# Tablero_Potencia.net
KiCad netlist of a schematic drawn in EAGLE
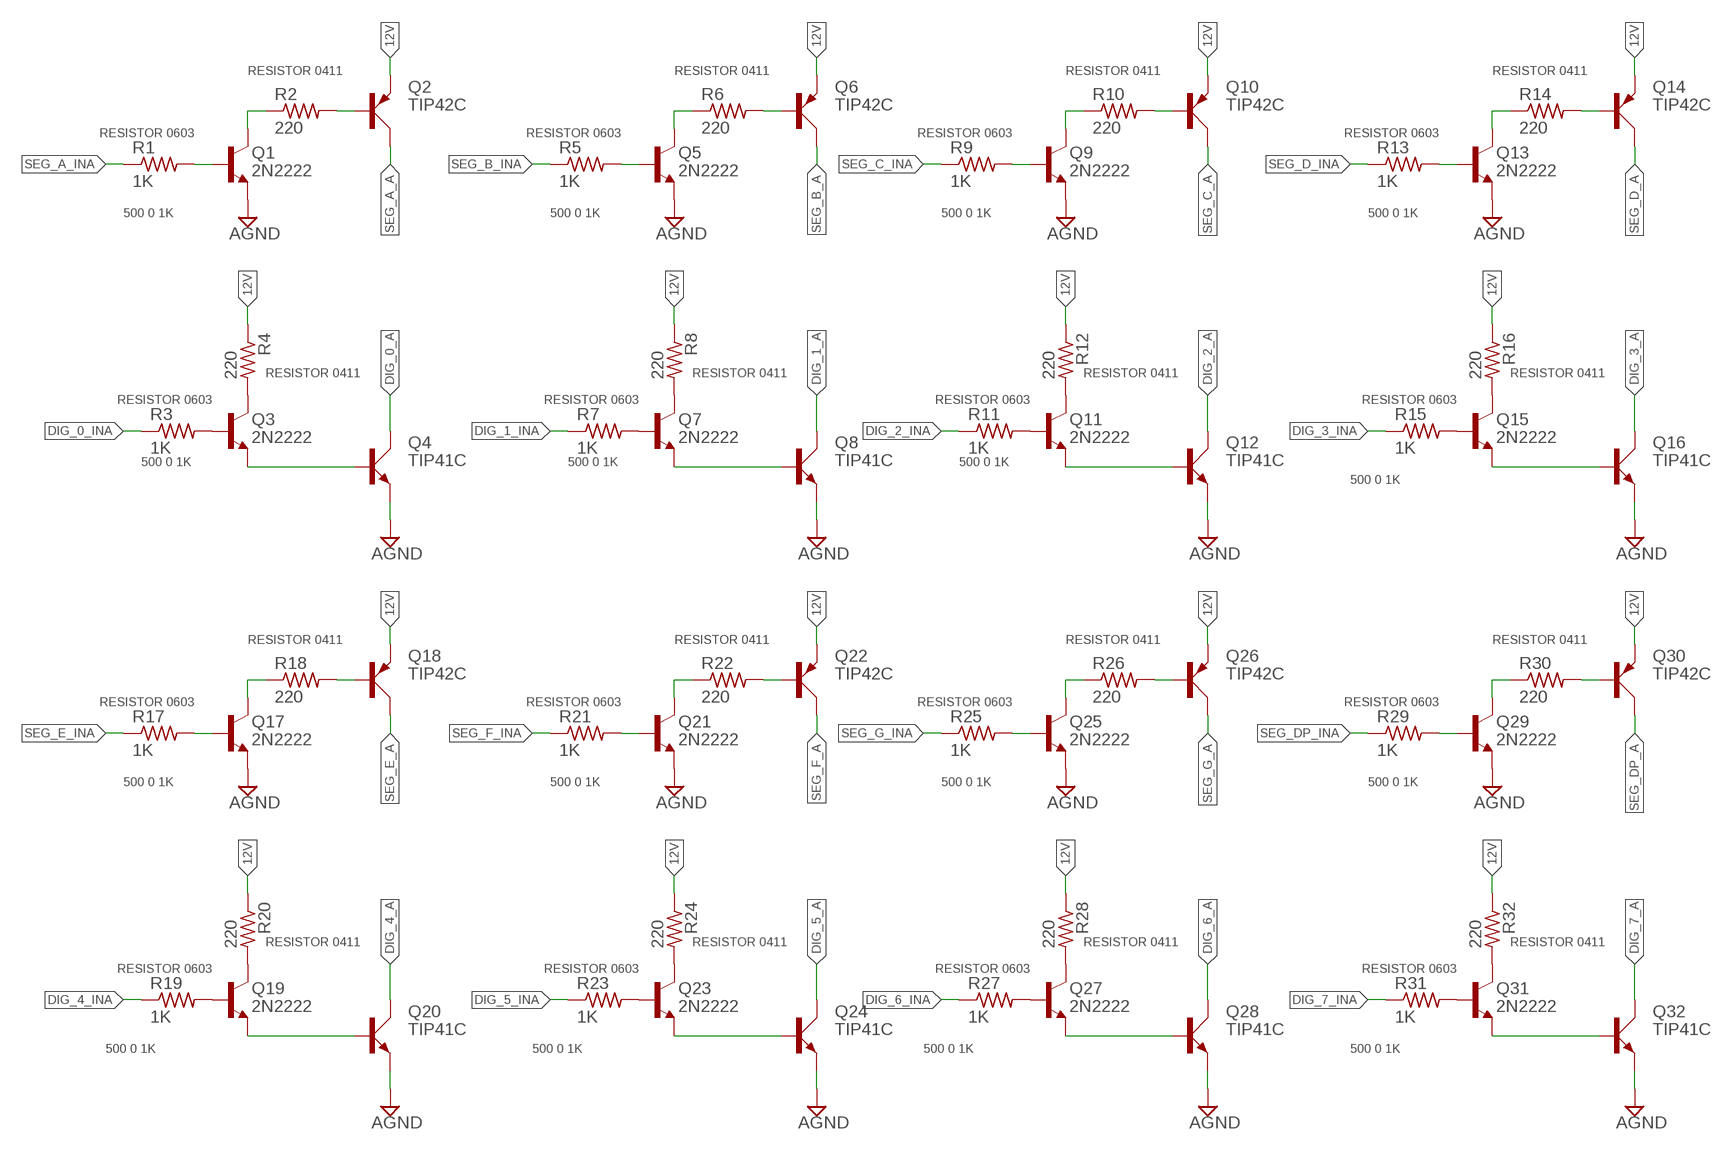
[diagram p0: schematic, sheet 1, part 1 of 2]
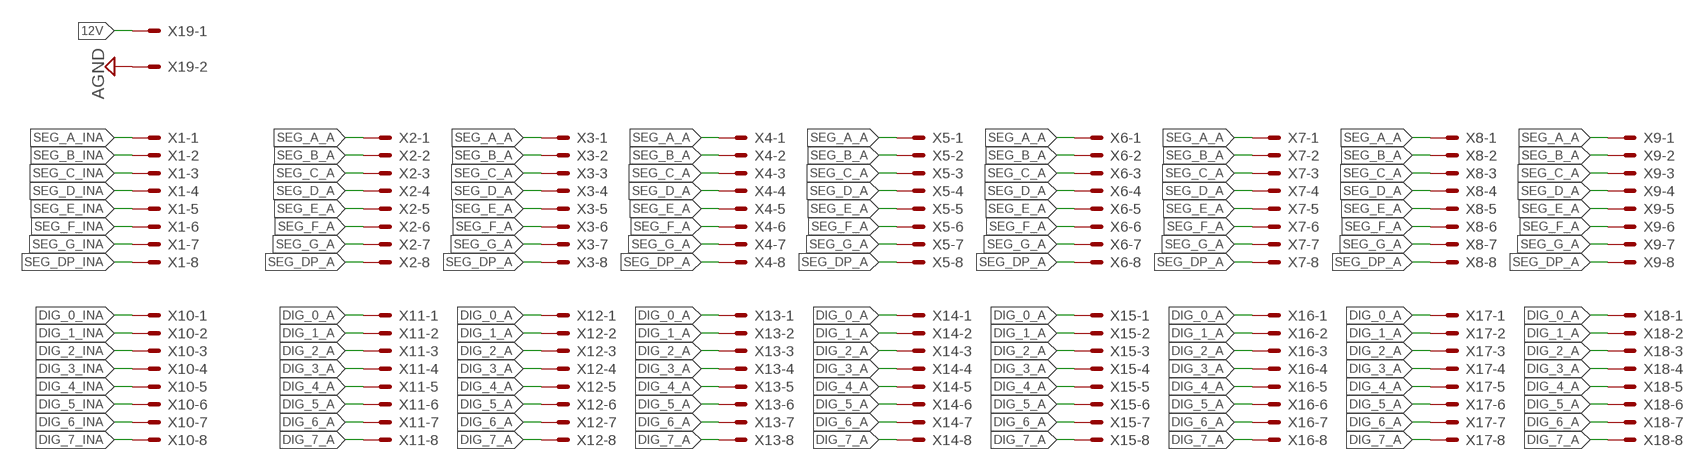
[diagram p1: schematic, sheet 1, part 2 of 2]

(export (version "E")
  (design (tool "Eeschema 10.0.6"))
  (components
    (comp (ref "Q1")
      (value "2N2222")
      (footprint "eagle-import:TO92")
      (libsource (lib "eagle-import") (part "BJT-NPNTO92"))
    )
    (comp (ref "Q2")
      (value "TIP42C")
      (footprint "eagle-import:TO220AV")
      (libsource (lib "eagle-import") (part "TIP42C"))
    )
    (comp (ref "Q3")
      (value "2N2222")
      (footprint "eagle-import:TO92")
      (libsource (lib "eagle-import") (part "BJT-NPNTO92"))
    )
    (comp (ref "Q4")
      (value "TIP41C")
      (footprint "eagle-import:TO220AV")
      (libsource (lib "eagle-import") (part "TIP41C"))
    )
    (comp (ref "Q5")
      (value "2N2222")
      (footprint "eagle-import:TO92")
      (libsource (lib "eagle-import") (part "BJT-NPNTO92"))
    )
    (comp (ref "Q6")
      (value "TIP42C")
      (footprint "eagle-import:TO220AV")
      (libsource (lib "eagle-import") (part "TIP42C"))
    )
    (comp (ref "Q7")
      (value "2N2222")
      (footprint "eagle-import:TO92")
      (libsource (lib "eagle-import") (part "BJT-NPNTO92"))
    )
    (comp (ref "Q8")
      (value "TIP41C")
      (footprint "eagle-import:TO220AV")
      (libsource (lib "eagle-import") (part "TIP41C"))
    )
    (comp (ref "Q9")
      (value "2N2222")
      (footprint "eagle-import:TO92")
      (libsource (lib "eagle-import") (part "BJT-NPNTO92"))
    )
    (comp (ref "Q10")
      (value "TIP42C")
      (footprint "eagle-import:TO220AV")
      (libsource (lib "eagle-import") (part "TIP42C"))
    )
    (comp (ref "Q11")
      (value "2N2222")
      (footprint "eagle-import:TO92")
      (libsource (lib "eagle-import") (part "BJT-NPNTO92"))
    )
    (comp (ref "Q12")
      (value "TIP41C")
      (footprint "eagle-import:TO220AV")
      (libsource (lib "eagle-import") (part "TIP41C"))
    )
    (comp (ref "Q13")
      (value "2N2222")
      (footprint "eagle-import:TO92")
      (libsource (lib "eagle-import") (part "BJT-NPNTO92"))
    )
    (comp (ref "Q14")
      (value "TIP42C")
      (footprint "eagle-import:TO220AV")
      (libsource (lib "eagle-import") (part "TIP42C"))
    )
    (comp (ref "Q15")
      (value "2N2222")
      (footprint "eagle-import:TO92")
      (libsource (lib "eagle-import") (part "BJT-NPNTO92"))
    )
    (comp (ref "Q16")
      (value "TIP41C")
      (footprint "eagle-import:TO220AV")
      (libsource (lib "eagle-import") (part "TIP41C"))
    )
    (comp (ref "Q17")
      (value "2N2222")
      (footprint "eagle-import:TO92")
      (libsource (lib "eagle-import") (part "BJT-NPNTO92"))
    )
    (comp (ref "Q18")
      (value "TIP42C")
      (footprint "eagle-import:TO220AV")
      (libsource (lib "eagle-import") (part "TIP42C"))
    )
    (comp (ref "Q19")
      (value "2N2222")
      (footprint "eagle-import:TO92")
      (libsource (lib "eagle-import") (part "BJT-NPNTO92"))
    )
    (comp (ref "Q20")
      (value "TIP41C")
      (footprint "eagle-import:TO220AV")
      (libsource (lib "eagle-import") (part "TIP41C"))
    )
    (comp (ref "Q21")
      (value "2N2222")
      (footprint "eagle-import:TO92")
      (libsource (lib "eagle-import") (part "BJT-NPNTO92"))
    )
    (comp (ref "Q22")
      (value "TIP42C")
      (footprint "eagle-import:TO220AV")
      (libsource (lib "eagle-import") (part "TIP42C"))
    )
    (comp (ref "Q23")
      (value "2N2222")
      (footprint "eagle-import:TO92")
      (libsource (lib "eagle-import") (part "BJT-NPNTO92"))
    )
    (comp (ref "Q24")
      (value "TIP41C")
      (footprint "eagle-import:TO220AV")
      (libsource (lib "eagle-import") (part "TIP41C"))
    )
    (comp (ref "Q25")
      (value "2N2222")
      (footprint "eagle-import:TO92")
      (libsource (lib "eagle-import") (part "BJT-NPNTO92"))
    )
    (comp (ref "Q26")
      (value "TIP42C")
      (footprint "eagle-import:TO220AV")
      (libsource (lib "eagle-import") (part "TIP42C"))
    )
    (comp (ref "Q27")
      (value "2N2222")
      (footprint "eagle-import:TO92")
      (libsource (lib "eagle-import") (part "BJT-NPNTO92"))
    )
    (comp (ref "Q28")
      (value "TIP41C")
      (footprint "eagle-import:TO220AV")
      (libsource (lib "eagle-import") (part "TIP41C"))
    )
    (comp (ref "Q29")
      (value "2N2222")
      (footprint "eagle-import:TO92")
      (libsource (lib "eagle-import") (part "BJT-NPNTO92"))
    )
    (comp (ref "Q30")
      (value "TIP42C")
      (footprint "eagle-import:TO220AV")
      (libsource (lib "eagle-import") (part "TIP42C"))
    )
    (comp (ref "Q31")
      (value "2N2222")
      (footprint "eagle-import:TO92")
      (libsource (lib "eagle-import") (part "BJT-NPNTO92"))
    )
    (comp (ref "Q32")
      (value "TIP41C")
      (footprint "eagle-import:TO220AV")
      (libsource (lib "eagle-import") (part "TIP41C"))
    )
    (comp (ref "R1")
      (value "1K")
      (footprint "eagle-import:R0603")
      (libsource (lib "eagle-import") (part "R-US_R0603"))
    )
    (comp (ref "R2")
      (value "220")
      (footprint "eagle-import:0411_15")
      (libsource (lib "eagle-import") (part "R-US_0411/15"))
    )
    (comp (ref "R3")
      (value "1K")
      (footprint "eagle-import:R0603")
      (libsource (lib "eagle-import") (part "R-US_R0603"))
    )
    (comp (ref "R4")
      (value "220")
      (footprint "eagle-import:0411_15")
      (libsource (lib "eagle-import") (part "R-US_0411/15"))
    )
    (comp (ref "R5")
      (value "1K")
      (footprint "eagle-import:R0603")
      (libsource (lib "eagle-import") (part "R-US_R0603"))
    )
    (comp (ref "R6")
      (value "220")
      (footprint "eagle-import:0411_15")
      (libsource (lib "eagle-import") (part "R-US_0411/15"))
    )
    (comp (ref "R7")
      (value "1K")
      (footprint "eagle-import:R0603")
      (libsource (lib "eagle-import") (part "R-US_R0603"))
    )
    (comp (ref "R8")
      (value "220")
      (footprint "eagle-import:0411_15")
      (libsource (lib "eagle-import") (part "R-US_0411/15"))
    )
    (comp (ref "R9")
      (value "1K")
      (footprint "eagle-import:R0603")
      (libsource (lib "eagle-import") (part "R-US_R0603"))
    )
    (comp (ref "R10")
      (value "220")
      (footprint "eagle-import:0411_15")
      (libsource (lib "eagle-import") (part "R-US_0411/15"))
    )
    (comp (ref "R11")
      (value "1K")
      (footprint "eagle-import:R0603")
      (libsource (lib "eagle-import") (part "R-US_R0603"))
    )
    (comp (ref "R12")
      (value "220")
      (footprint "eagle-import:0411_15")
      (libsource (lib "eagle-import") (part "R-US_0411/15"))
    )
    (comp (ref "R13")
      (value "1K")
      (footprint "eagle-import:R0603")
      (libsource (lib "eagle-import") (part "R-US_R0603"))
    )
    (comp (ref "R14")
      (value "220")
      (footprint "eagle-import:0411_15")
      (libsource (lib "eagle-import") (part "R-US_0411/15"))
    )
    (comp (ref "R15")
      (value "1K")
      (footprint "eagle-import:R0603")
      (libsource (lib "eagle-import") (part "R-US_R0603"))
    )
    (comp (ref "R16")
      (value "220")
      (footprint "eagle-import:0411_15")
      (libsource (lib "eagle-import") (part "R-US_0411/15"))
    )
    (comp (ref "R17")
      (value "1K")
      (footprint "eagle-import:R0603")
      (libsource (lib "eagle-import") (part "R-US_R0603"))
    )
    (comp (ref "R18")
      (value "220")
      (footprint "eagle-import:0411_15")
      (libsource (lib "eagle-import") (part "R-US_0411/15"))
    )
    (comp (ref "R19")
      (value "1K")
      (footprint "eagle-import:R0603")
      (libsource (lib "eagle-import") (part "R-US_R0603"))
    )
    (comp (ref "R20")
      (value "220")
      (footprint "eagle-import:0411_15")
      (libsource (lib "eagle-import") (part "R-US_0411/15"))
    )
    (comp (ref "R21")
      (value "1K")
      (footprint "eagle-import:R0603")
      (libsource (lib "eagle-import") (part "R-US_R0603"))
    )
    (comp (ref "R22")
      (value "220")
      (footprint "eagle-import:0411_15")
      (libsource (lib "eagle-import") (part "R-US_0411/15"))
    )
    (comp (ref "R23")
      (value "1K")
      (footprint "eagle-import:R0603")
      (libsource (lib "eagle-import") (part "R-US_R0603"))
    )
    (comp (ref "R24")
      (value "220")
      (footprint "eagle-import:0411_15")
      (libsource (lib "eagle-import") (part "R-US_0411/15"))
    )
    (comp (ref "R25")
      (value "1K")
      (footprint "eagle-import:R0603")
      (libsource (lib "eagle-import") (part "R-US_R0603"))
    )
    (comp (ref "R26")
      (value "220")
      (footprint "eagle-import:0411_15")
      (libsource (lib "eagle-import") (part "R-US_0411/15"))
    )
    (comp (ref "R27")
      (value "1K")
      (footprint "eagle-import:R0603")
      (libsource (lib "eagle-import") (part "R-US_R0603"))
    )
    (comp (ref "R28")
      (value "220")
      (footprint "eagle-import:0411_15")
      (libsource (lib "eagle-import") (part "R-US_0411/15"))
    )
    (comp (ref "R29")
      (value "1K")
      (footprint "eagle-import:R0603")
      (libsource (lib "eagle-import") (part "R-US_R0603"))
    )
    (comp (ref "R30")
      (value "220")
      (footprint "eagle-import:0411_15")
      (libsource (lib "eagle-import") (part "R-US_0411/15"))
    )
    (comp (ref "R31")
      (value "1K")
      (footprint "eagle-import:R0603")
      (libsource (lib "eagle-import") (part "R-US_R0603"))
    )
    (comp (ref "R32")
      (value "220")
      (footprint "eagle-import:0411_15")
      (libsource (lib "eagle-import") (part "R-US_0411/15"))
    )
    (comp (ref "X1")
      (value "KK-156-8")
      (footprint "eagle-import:KK-156-8")
      (fields (field (name "MF") "MOLEX"))
      (libsource (lib "eagle-import") (part "KK-156-8"))
    )
    (comp (ref "X2")
      (value "KK-156-8")
      (footprint "eagle-import:KK-156-8")
      (fields (field (name "MF") "MOLEX"))
      (libsource (lib "eagle-import") (part "KK-156-8"))
    )
    (comp (ref "X3")
      (value "KK-156-8")
      (footprint "eagle-import:KK-156-8")
      (fields (field (name "MF") "MOLEX"))
      (libsource (lib "eagle-import") (part "KK-156-8"))
    )
    (comp (ref "X4")
      (value "KK-156-8")
      (footprint "eagle-import:KK-156-8")
      (fields (field (name "MF") "MOLEX"))
      (libsource (lib "eagle-import") (part "KK-156-8"))
    )
    (comp (ref "X5")
      (value "KK-156-8")
      (footprint "eagle-import:KK-156-8")
      (fields (field (name "MF") "MOLEX"))
      (libsource (lib "eagle-import") (part "KK-156-8"))
    )
    (comp (ref "X6")
      (value "KK-156-8")
      (footprint "eagle-import:KK-156-8")
      (fields (field (name "MF") "MOLEX"))
      (libsource (lib "eagle-import") (part "KK-156-8"))
    )
    (comp (ref "X7")
      (value "KK-156-8")
      (footprint "eagle-import:KK-156-8")
      (fields (field (name "MF") "MOLEX"))
      (libsource (lib "eagle-import") (part "KK-156-8"))
    )
    (comp (ref "X8")
      (value "KK-156-8")
      (footprint "eagle-import:KK-156-8")
      (fields (field (name "MF") "MOLEX"))
      (libsource (lib "eagle-import") (part "KK-156-8"))
    )
    (comp (ref "X9")
      (value "KK-156-8")
      (footprint "eagle-import:KK-156-8")
      (fields (field (name "MF") "MOLEX"))
      (libsource (lib "eagle-import") (part "KK-156-8"))
    )
    (comp (ref "X10")
      (value "KK-156-8")
      (footprint "eagle-import:KK-156-8")
      (fields (field (name "MF") "MOLEX"))
      (libsource (lib "eagle-import") (part "KK-156-8"))
    )
    (comp (ref "X11")
      (value "KK-156-8")
      (footprint "eagle-import:KK-156-8")
      (fields (field (name "MF") "MOLEX"))
      (libsource (lib "eagle-import") (part "KK-156-8"))
    )
    (comp (ref "X12")
      (value "KK-156-8")
      (footprint "eagle-import:KK-156-8")
      (fields (field (name "MF") "MOLEX"))
      (libsource (lib "eagle-import") (part "KK-156-8"))
    )
    (comp (ref "X13")
      (value "KK-156-8")
      (footprint "eagle-import:KK-156-8")
      (fields (field (name "MF") "MOLEX"))
      (libsource (lib "eagle-import") (part "KK-156-8"))
    )
    (comp (ref "X14")
      (value "KK-156-8")
      (footprint "eagle-import:KK-156-8")
      (fields (field (name "MF") "MOLEX"))
      (libsource (lib "eagle-import") (part "KK-156-8"))
    )
    (comp (ref "X15")
      (value "KK-156-8")
      (footprint "eagle-import:KK-156-8")
      (fields (field (name "MF") "MOLEX"))
      (libsource (lib "eagle-import") (part "KK-156-8"))
    )
    (comp (ref "X16")
      (value "KK-156-8")
      (footprint "eagle-import:KK-156-8")
      (fields (field (name "MF") "MOLEX"))
      (libsource (lib "eagle-import") (part "KK-156-8"))
    )
    (comp (ref "X17")
      (value "KK-156-8")
      (footprint "eagle-import:KK-156-8")
      (fields (field (name "MF") "MOLEX"))
      (libsource (lib "eagle-import") (part "KK-156-8"))
    )
    (comp (ref "X18")
      (value "KK-156-8")
      (footprint "eagle-import:KK-156-8")
      (fields (field (name "MF") "MOLEX"))
      (libsource (lib "eagle-import") (part "KK-156-8"))
    )
    (comp (ref "X19")
      (value "KK-156-2")
      (footprint "eagle-import:KK-156-2")
      (fields (field (name "MF") "MOLEX"))
      (libsource (lib "eagle-import") (part "KK-156-2"))
    )
  )
  (nets
    (net (code "1") (name "12V") (class "Default")
      (node (ref "Q10") (pin "E") (pinfunction "E_E") (pintype "passive"))
      (node (ref "Q14") (pin "E") (pinfunction "E_E") (pintype "passive"))
      (node (ref "Q18") (pin "E") (pinfunction "E_E") (pintype "passive"))
      (node (ref "Q2") (pin "E") (pinfunction "E_E") (pintype "passive"))
      (node (ref "Q22") (pin "E") (pinfunction "E_E") (pintype "passive"))
      (node (ref "Q26") (pin "E") (pinfunction "E_E") (pintype "passive"))
      (node (ref "Q30") (pin "E") (pinfunction "E_E") (pintype "passive"))
      (node (ref "Q6") (pin "E") (pinfunction "E_E") (pintype "passive"))
      (node (ref "R12") (pin "1") (pinfunction "1_1") (pintype "passive"))
      (node (ref "R16") (pin "1") (pinfunction "1_1") (pintype "passive"))
      (node (ref "R20") (pin "1") (pinfunction "1_1") (pintype "passive"))
      (node (ref "R24") (pin "1") (pinfunction "1_1") (pintype "passive"))
      (node (ref "R28") (pin "1") (pinfunction "1_1") (pintype "passive"))
      (node (ref "R32") (pin "1") (pinfunction "1_1") (pintype "passive"))
      (node (ref "R4") (pin "1") (pinfunction "1_1") (pintype "passive"))
      (node (ref "R8") (pin "1") (pinfunction "1_1") (pintype "passive"))
      (node (ref "X19") (pin "1") (pinfunction "S_1") (pintype "passive"))
    )
    (net (code "2") (name "AGND") (class "Default")
      (node (ref "Q1") (pin "3") (pinfunction "E_3") (pintype "passive"))
      (node (ref "Q12") (pin "E") (pinfunction "E_E") (pintype "passive"))
      (node (ref "Q13") (pin "3") (pinfunction "E_3") (pintype "passive"))
      (node (ref "Q16") (pin "E") (pinfunction "E_E") (pintype "passive"))
      (node (ref "Q17") (pin "3") (pinfunction "E_3") (pintype "passive"))
      (node (ref "Q20") (pin "E") (pinfunction "E_E") (pintype "passive"))
      (node (ref "Q21") (pin "3") (pinfunction "E_3") (pintype "passive"))
      (node (ref "Q24") (pin "E") (pinfunction "E_E") (pintype "passive"))
      (node (ref "Q25") (pin "3") (pinfunction "E_3") (pintype "passive"))
      (node (ref "Q28") (pin "E") (pinfunction "E_E") (pintype "passive"))
      (node (ref "Q29") (pin "3") (pinfunction "E_3") (pintype "passive"))
      (node (ref "Q32") (pin "E") (pinfunction "E_E") (pintype "passive"))
      (node (ref "Q4") (pin "E") (pinfunction "E_E") (pintype "passive"))
      (node (ref "Q5") (pin "3") (pinfunction "E_3") (pintype "passive"))
      (node (ref "Q8") (pin "E") (pinfunction "E_E") (pintype "passive"))
      (node (ref "Q9") (pin "3") (pinfunction "E_3") (pintype "passive"))
      (node (ref "X19") (pin "2") (pinfunction "S_2") (pintype "passive"))
    )
    (net (code "3") (name "DIG_0_A") (class "Default")
      (node (ref "Q4") (pin "C") (pinfunction "C_C") (pintype "passive"))
      (node (ref "X11") (pin "1") (pinfunction "S_1") (pintype "passive"))
      (node (ref "X12") (pin "1") (pinfunction "S_1") (pintype "passive"))
      (node (ref "X13") (pin "1") (pinfunction "S_1") (pintype "passive"))
      (node (ref "X14") (pin "1") (pinfunction "S_1") (pintype "passive"))
      (node (ref "X15") (pin "1") (pinfunction "S_1") (pintype "passive"))
      (node (ref "X16") (pin "1") (pinfunction "S_1") (pintype "passive"))
      (node (ref "X17") (pin "1") (pinfunction "S_1") (pintype "passive"))
      (node (ref "X18") (pin "1") (pinfunction "S_1") (pintype "passive"))
    )
    (net (code "4") (name "DIG_0_INA") (class "Default")
      (node (ref "R3") (pin "1") (pinfunction "1_1") (pintype "passive"))
      (node (ref "X10") (pin "1") (pinfunction "S_1") (pintype "passive"))
    )
    (net (code "5") (name "DIG_1_A") (class "Default")
      (node (ref "Q8") (pin "C") (pinfunction "C_C") (pintype "passive"))
      (node (ref "X11") (pin "2") (pinfunction "S_2") (pintype "passive"))
      (node (ref "X12") (pin "2") (pinfunction "S_2") (pintype "passive"))
      (node (ref "X13") (pin "2") (pinfunction "S_2") (pintype "passive"))
      (node (ref "X14") (pin "2") (pinfunction "S_2") (pintype "passive"))
      (node (ref "X15") (pin "2") (pinfunction "S_2") (pintype "passive"))
      (node (ref "X16") (pin "2") (pinfunction "S_2") (pintype "passive"))
      (node (ref "X17") (pin "2") (pinfunction "S_2") (pintype "passive"))
      (node (ref "X18") (pin "2") (pinfunction "S_2") (pintype "passive"))
    )
    (net (code "6") (name "DIG_1_INA") (class "Default")
      (node (ref "R7") (pin "1") (pinfunction "1_1") (pintype "passive"))
      (node (ref "X10") (pin "2") (pinfunction "S_2") (pintype "passive"))
    )
    (net (code "7") (name "DIG_2_A") (class "Default")
      (node (ref "Q12") (pin "C") (pinfunction "C_C") (pintype "passive"))
      (node (ref "X11") (pin "3") (pinfunction "S_3") (pintype "passive"))
      (node (ref "X12") (pin "3") (pinfunction "S_3") (pintype "passive"))
      (node (ref "X13") (pin "3") (pinfunction "S_3") (pintype "passive"))
      (node (ref "X14") (pin "3") (pinfunction "S_3") (pintype "passive"))
      (node (ref "X15") (pin "3") (pinfunction "S_3") (pintype "passive"))
      (node (ref "X16") (pin "3") (pinfunction "S_3") (pintype "passive"))
      (node (ref "X17") (pin "3") (pinfunction "S_3") (pintype "passive"))
      (node (ref "X18") (pin "3") (pinfunction "S_3") (pintype "passive"))
    )
    (net (code "8") (name "DIG_2_INA") (class "Default")
      (node (ref "R11") (pin "1") (pinfunction "1_1") (pintype "passive"))
      (node (ref "X10") (pin "3") (pinfunction "S_3") (pintype "passive"))
    )
    (net (code "9") (name "DIG_3_A") (class "Default")
      (node (ref "Q16") (pin "C") (pinfunction "C_C") (pintype "passive"))
      (node (ref "X11") (pin "4") (pinfunction "S_4") (pintype "passive"))
      (node (ref "X12") (pin "4") (pinfunction "S_4") (pintype "passive"))
      (node (ref "X13") (pin "4") (pinfunction "S_4") (pintype "passive"))
      (node (ref "X14") (pin "4") (pinfunction "S_4") (pintype "passive"))
      (node (ref "X15") (pin "4") (pinfunction "S_4") (pintype "passive"))
      (node (ref "X16") (pin "4") (pinfunction "S_4") (pintype "passive"))
      (node (ref "X17") (pin "4") (pinfunction "S_4") (pintype "passive"))
      (node (ref "X18") (pin "4") (pinfunction "S_4") (pintype "passive"))
    )
    (net (code "10") (name "DIG_3_INA") (class "Default")
      (node (ref "R15") (pin "1") (pinfunction "1_1") (pintype "passive"))
      (node (ref "X10") (pin "4") (pinfunction "S_4") (pintype "passive"))
    )
    (net (code "11") (name "DIG_4_A") (class "Default")
      (node (ref "Q20") (pin "C") (pinfunction "C_C") (pintype "passive"))
      (node (ref "X11") (pin "5") (pinfunction "S_5") (pintype "passive"))
      (node (ref "X12") (pin "5") (pinfunction "S_5") (pintype "passive"))
      (node (ref "X13") (pin "5") (pinfunction "S_5") (pintype "passive"))
      (node (ref "X14") (pin "5") (pinfunction "S_5") (pintype "passive"))
      (node (ref "X15") (pin "5") (pinfunction "S_5") (pintype "passive"))
      (node (ref "X16") (pin "5") (pinfunction "S_5") (pintype "passive"))
      (node (ref "X17") (pin "5") (pinfunction "S_5") (pintype "passive"))
      (node (ref "X18") (pin "5") (pinfunction "S_5") (pintype "passive"))
    )
    (net (code "12") (name "DIG_4_INA") (class "Default")
      (node (ref "R19") (pin "1") (pinfunction "1_1") (pintype "passive"))
      (node (ref "X10") (pin "5") (pinfunction "S_5") (pintype "passive"))
    )
    (net (code "13") (name "DIG_5_A") (class "Default")
      (node (ref "Q24") (pin "C") (pinfunction "C_C") (pintype "passive"))
      (node (ref "X11") (pin "6") (pinfunction "S_6") (pintype "passive"))
      (node (ref "X12") (pin "6") (pinfunction "S_6") (pintype "passive"))
      (node (ref "X13") (pin "6") (pinfunction "S_6") (pintype "passive"))
      (node (ref "X14") (pin "6") (pinfunction "S_6") (pintype "passive"))
      (node (ref "X15") (pin "6") (pinfunction "S_6") (pintype "passive"))
      (node (ref "X16") (pin "6") (pinfunction "S_6") (pintype "passive"))
      (node (ref "X17") (pin "6") (pinfunction "S_6") (pintype "passive"))
      (node (ref "X18") (pin "6") (pinfunction "S_6") (pintype "passive"))
    )
    (net (code "14") (name "DIG_5_INA") (class "Default")
      (node (ref "R23") (pin "1") (pinfunction "1_1") (pintype "passive"))
      (node (ref "X10") (pin "6") (pinfunction "S_6") (pintype "passive"))
    )
    (net (code "15") (name "DIG_6_A") (class "Default")
      (node (ref "Q28") (pin "C") (pinfunction "C_C") (pintype "passive"))
      (node (ref "X11") (pin "7") (pinfunction "S_7") (pintype "passive"))
      (node (ref "X12") (pin "7") (pinfunction "S_7") (pintype "passive"))
      (node (ref "X13") (pin "7") (pinfunction "S_7") (pintype "passive"))
      (node (ref "X14") (pin "7") (pinfunction "S_7") (pintype "passive"))
      (node (ref "X15") (pin "7") (pinfunction "S_7") (pintype "passive"))
      (node (ref "X16") (pin "7") (pinfunction "S_7") (pintype "passive"))
      (node (ref "X17") (pin "7") (pinfunction "S_7") (pintype "passive"))
      (node (ref "X18") (pin "7") (pinfunction "S_7") (pintype "passive"))
    )
    (net (code "16") (name "DIG_6_INA") (class "Default")
      (node (ref "R27") (pin "1") (pinfunction "1_1") (pintype "passive"))
      (node (ref "X10") (pin "7") (pinfunction "S_7") (pintype "passive"))
    )
    (net (code "17") (name "DIG_7_A") (class "Default")
      (node (ref "Q32") (pin "C") (pinfunction "C_C") (pintype "passive"))
      (node (ref "X11") (pin "8") (pinfunction "S_8") (pintype "passive"))
      (node (ref "X12") (pin "8") (pinfunction "S_8") (pintype "passive"))
      (node (ref "X13") (pin "8") (pinfunction "S_8") (pintype "passive"))
      (node (ref "X14") (pin "8") (pinfunction "S_8") (pintype "passive"))
      (node (ref "X15") (pin "8") (pinfunction "S_8") (pintype "passive"))
      (node (ref "X16") (pin "8") (pinfunction "S_8") (pintype "passive"))
      (node (ref "X17") (pin "8") (pinfunction "S_8") (pintype "passive"))
      (node (ref "X18") (pin "8") (pinfunction "S_8") (pintype "passive"))
    )
    (net (code "18") (name "DIG_7_INA") (class "Default")
      (node (ref "R31") (pin "1") (pinfunction "1_1") (pintype "passive"))
      (node (ref "X10") (pin "8") (pinfunction "S_8") (pintype "passive"))
    )
    (net (code "19") (name "Net-(Q1-B)") (class "Default")
      (node (ref "Q1") (pin "2") (pinfunction "B_2") (pintype "passive"))
      (node (ref "R1") (pin "2") (pinfunction "2_2") (pintype "passive"))
    )
    (net (code "20") (name "Net-(Q1-C)") (class "Default")
      (node (ref "Q1") (pin "1") (pinfunction "C_1") (pintype "passive"))
      (node (ref "R2") (pin "1") (pinfunction "1_1") (pintype "passive"))
    )
    (net (code "21") (name "Net-(Q2-PadB)") (class "Default")
      (node (ref "Q2") (pin "B") (pinfunction "B_B") (pintype "passive"))
      (node (ref "R2") (pin "2") (pinfunction "2_2") (pintype "passive"))
    )
    (net (code "22") (name "Net-(Q3-B)") (class "Default")
      (node (ref "Q3") (pin "2") (pinfunction "B_2") (pintype "passive"))
      (node (ref "R3") (pin "2") (pinfunction "2_2") (pintype "passive"))
    )
    (net (code "23") (name "Net-(Q3-C)") (class "Default")
      (node (ref "Q3") (pin "1") (pinfunction "C_1") (pintype "passive"))
      (node (ref "R4") (pin "2") (pinfunction "2_2") (pintype "passive"))
    )
    (net (code "24") (name "Net-(Q3-E)") (class "Default")
      (node (ref "Q3") (pin "3") (pinfunction "E_3") (pintype "passive"))
      (node (ref "Q4") (pin "B") (pinfunction "B_B") (pintype "passive"))
    )
    (net (code "25") (name "Net-(Q5-B)") (class "Default")
      (node (ref "Q5") (pin "2") (pinfunction "B_2") (pintype "passive"))
      (node (ref "R5") (pin "2") (pinfunction "2_2") (pintype "passive"))
    )
    (net (code "26") (name "Net-(Q5-C)") (class "Default")
      (node (ref "Q5") (pin "1") (pinfunction "C_1") (pintype "passive"))
      (node (ref "R6") (pin "1") (pinfunction "1_1") (pintype "passive"))
    )
    (net (code "27") (name "Net-(Q6-PadB)") (class "Default")
      (node (ref "Q6") (pin "B") (pinfunction "B_B") (pintype "passive"))
      (node (ref "R6") (pin "2") (pinfunction "2_2") (pintype "passive"))
    )
    (net (code "28") (name "Net-(Q7-B)") (class "Default")
      (node (ref "Q7") (pin "2") (pinfunction "B_2") (pintype "passive"))
      (node (ref "R7") (pin "2") (pinfunction "2_2") (pintype "passive"))
    )
    (net (code "29") (name "Net-(Q7-C)") (class "Default")
      (node (ref "Q7") (pin "1") (pinfunction "C_1") (pintype "passive"))
      (node (ref "R8") (pin "2") (pinfunction "2_2") (pintype "passive"))
    )
    (net (code "30") (name "Net-(Q7-E)") (class "Default")
      (node (ref "Q7") (pin "3") (pinfunction "E_3") (pintype "passive"))
      (node (ref "Q8") (pin "B") (pinfunction "B_B") (pintype "passive"))
    )
    (net (code "31") (name "Net-(Q9-B)") (class "Default")
      (node (ref "Q9") (pin "2") (pinfunction "B_2") (pintype "passive"))
      (node (ref "R9") (pin "2") (pinfunction "2_2") (pintype "passive"))
    )
    (net (code "32") (name "Net-(Q9-C)") (class "Default")
      (node (ref "Q9") (pin "1") (pinfunction "C_1") (pintype "passive"))
      (node (ref "R10") (pin "1") (pinfunction "1_1") (pintype "passive"))
    )
    (net (code "33") (name "Net-(Q10-PadB)") (class "Default")
      (node (ref "Q10") (pin "B") (pinfunction "B_B") (pintype "passive"))
      (node (ref "R10") (pin "2") (pinfunction "2_2") (pintype "passive"))
    )
    (net (code "34") (name "Net-(Q11-B)") (class "Default")
      (node (ref "Q11") (pin "2") (pinfunction "B_2") (pintype "passive"))
      (node (ref "R11") (pin "2") (pinfunction "2_2") (pintype "passive"))
    )
    (net (code "35") (name "Net-(Q11-C)") (class "Default")
      (node (ref "Q11") (pin "1") (pinfunction "C_1") (pintype "passive"))
      (node (ref "R12") (pin "2") (pinfunction "2_2") (pintype "passive"))
    )
    (net (code "36") (name "Net-(Q11-E)") (class "Default")
      (node (ref "Q11") (pin "3") (pinfunction "E_3") (pintype "passive"))
      (node (ref "Q12") (pin "B") (pinfunction "B_B") (pintype "passive"))
    )
    (net (code "37") (name "Net-(Q13-B)") (class "Default")
      (node (ref "Q13") (pin "2") (pinfunction "B_2") (pintype "passive"))
      (node (ref "R13") (pin "2") (pinfunction "2_2") (pintype "passive"))
    )
    (net (code "38") (name "Net-(Q13-C)") (class "Default")
      (node (ref "Q13") (pin "1") (pinfunction "C_1") (pintype "passive"))
      (node (ref "R14") (pin "1") (pinfunction "1_1") (pintype "passive"))
    )
    (net (code "39") (name "Net-(Q14-PadB)") (class "Default")
      (node (ref "Q14") (pin "B") (pinfunction "B_B") (pintype "passive"))
      (node (ref "R14") (pin "2") (pinfunction "2_2") (pintype "passive"))
    )
    (net (code "40") (name "Net-(Q15-B)") (class "Default")
      (node (ref "Q15") (pin "2") (pinfunction "B_2") (pintype "passive"))
      (node (ref "R15") (pin "2") (pinfunction "2_2") (pintype "passive"))
    )
    (net (code "41") (name "Net-(Q15-C)") (class "Default")
      (node (ref "Q15") (pin "1") (pinfunction "C_1") (pintype "passive"))
      (node (ref "R16") (pin "2") (pinfunction "2_2") (pintype "passive"))
    )
    (net (code "42") (name "Net-(Q15-E)") (class "Default")
      (node (ref "Q15") (pin "3") (pinfunction "E_3") (pintype "passive"))
      (node (ref "Q16") (pin "B") (pinfunction "B_B") (pintype "passive"))
    )
    (net (code "43") (name "Net-(Q17-B)") (class "Default")
      (node (ref "Q17") (pin "2") (pinfunction "B_2") (pintype "passive"))
      (node (ref "R17") (pin "2") (pinfunction "2_2") (pintype "passive"))
    )
    (net (code "44") (name "Net-(Q17-C)") (class "Default")
      (node (ref "Q17") (pin "1") (pinfunction "C_1") (pintype "passive"))
      (node (ref "R18") (pin "1") (pinfunction "1_1") (pintype "passive"))
    )
    (net (code "45") (name "Net-(Q18-PadB)") (class "Default")
      (node (ref "Q18") (pin "B") (pinfunction "B_B") (pintype "passive"))
      (node (ref "R18") (pin "2") (pinfunction "2_2") (pintype "passive"))
    )
    (net (code "46") (name "Net-(Q19-B)") (class "Default")
      (node (ref "Q19") (pin "2") (pinfunction "B_2") (pintype "passive"))
      (node (ref "R19") (pin "2") (pinfunction "2_2") (pintype "passive"))
    )
    (net (code "47") (name "Net-(Q19-C)") (class "Default")
      (node (ref "Q19") (pin "1") (pinfunction "C_1") (pintype "passive"))
      (node (ref "R20") (pin "2") (pinfunction "2_2") (pintype "passive"))
    )
    (net (code "48") (name "Net-(Q19-E)") (class "Default")
      (node (ref "Q19") (pin "3") (pinfunction "E_3") (pintype "passive"))
      (node (ref "Q20") (pin "B") (pinfunction "B_B") (pintype "passive"))
    )
    (net (code "49") (name "Net-(Q21-B)") (class "Default")
      (node (ref "Q21") (pin "2") (pinfunction "B_2") (pintype "passive"))
      (node (ref "R21") (pin "2") (pinfunction "2_2") (pintype "passive"))
    )
    (net (code "50") (name "Net-(Q21-C)") (class "Default")
      (node (ref "Q21") (pin "1") (pinfunction "C_1") (pintype "passive"))
      (node (ref "R22") (pin "1") (pinfunction "1_1") (pintype "passive"))
    )
    (net (code "51") (name "Net-(Q22-PadB)") (class "Default")
      (node (ref "Q22") (pin "B") (pinfunction "B_B") (pintype "passive"))
      (node (ref "R22") (pin "2") (pinfunction "2_2") (pintype "passive"))
    )
    (net (code "52") (name "Net-(Q23-B)") (class "Default")
      (node (ref "Q23") (pin "2") (pinfunction "B_2") (pintype "passive"))
      (node (ref "R23") (pin "2") (pinfunction "2_2") (pintype "passive"))
    )
    (net (code "53") (name "Net-(Q23-C)") (class "Default")
      (node (ref "Q23") (pin "1") (pinfunction "C_1") (pintype "passive"))
      (node (ref "R24") (pin "2") (pinfunction "2_2") (pintype "passive"))
    )
    (net (code "54") (name "Net-(Q23-E)") (class "Default")
      (node (ref "Q23") (pin "3") (pinfunction "E_3") (pintype "passive"))
      (node (ref "Q24") (pin "B") (pinfunction "B_B") (pintype "passive"))
    )
    (net (code "55") (name "Net-(Q25-B)") (class "Default")
      (node (ref "Q25") (pin "2") (pinfunction "B_2") (pintype "passive"))
      (node (ref "R25") (pin "2") (pinfunction "2_2") (pintype "passive"))
    )
    (net (code "56") (name "Net-(Q25-C)") (class "Default")
      (node (ref "Q25") (pin "1") (pinfunction "C_1") (pintype "passive"))
      (node (ref "R26") (pin "1") (pinfunction "1_1") (pintype "passive"))
    )
    (net (code "57") (name "Net-(Q26-PadB)") (class "Default")
      (node (ref "Q26") (pin "B") (pinfunction "B_B") (pintype "passive"))
      (node (ref "R26") (pin "2") (pinfunction "2_2") (pintype "passive"))
    )
    (net (code "58") (name "Net-(Q27-B)") (class "Default")
      (node (ref "Q27") (pin "2") (pinfunction "B_2") (pintype "passive"))
      (node (ref "R27") (pin "2") (pinfunction "2_2") (pintype "passive"))
    )
    (net (code "59") (name "Net-(Q27-C)") (class "Default")
      (node (ref "Q27") (pin "1") (pinfunction "C_1") (pintype "passive"))
      (node (ref "R28") (pin "2") (pinfunction "2_2") (pintype "passive"))
    )
    (net (code "60") (name "Net-(Q27-E)") (class "Default")
      (node (ref "Q27") (pin "3") (pinfunction "E_3") (pintype "passive"))
      (node (ref "Q28") (pin "B") (pinfunction "B_B") (pintype "passive"))
    )
    (net (code "61") (name "Net-(Q29-B)") (class "Default")
      (node (ref "Q29") (pin "2") (pinfunction "B_2") (pintype "passive"))
      (node (ref "R29") (pin "2") (pinfunction "2_2") (pintype "passive"))
    )
    (net (code "62") (name "Net-(Q29-C)") (class "Default")
      (node (ref "Q29") (pin "1") (pinfunction "C_1") (pintype "passive"))
      (node (ref "R30") (pin "1") (pinfunction "1_1") (pintype "passive"))
    )
    (net (code "63") (name "Net-(Q30-PadB)") (class "Default")
      (node (ref "Q30") (pin "B") (pinfunction "B_B") (pintype "passive"))
      (node (ref "R30") (pin "2") (pinfunction "2_2") (pintype "passive"))
    )
    (net (code "64") (name "Net-(Q31-B)") (class "Default")
      (node (ref "Q31") (pin "2") (pinfunction "B_2") (pintype "passive"))
      (node (ref "R31") (pin "2") (pinfunction "2_2") (pintype "passive"))
    )
    (net (code "65") (name "Net-(Q31-C)") (class "Default")
      (node (ref "Q31") (pin "1") (pinfunction "C_1") (pintype "passive"))
      (node (ref "R32") (pin "2") (pinfunction "2_2") (pintype "passive"))
    )
    (net (code "66") (name "Net-(Q31-E)") (class "Default")
      (node (ref "Q31") (pin "3") (pinfunction "E_3") (pintype "passive"))
      (node (ref "Q32") (pin "B") (pinfunction "B_B") (pintype "passive"))
    )
    (net (code "67") (name "SEG_A_A") (class "Default")
      (node (ref "Q2") (pin "C") (pinfunction "C_C") (pintype "passive"))
      (node (ref "X2") (pin "1") (pinfunction "S_1") (pintype "passive"))
      (node (ref "X3") (pin "1") (pinfunction "S_1") (pintype "passive"))
      (node (ref "X4") (pin "1") (pinfunction "S_1") (pintype "passive"))
      (node (ref "X5") (pin "1") (pinfunction "S_1") (pintype "passive"))
      (node (ref "X6") (pin "1") (pinfunction "S_1") (pintype "passive"))
      (node (ref "X7") (pin "1") (pinfunction "S_1") (pintype "passive"))
      (node (ref "X8") (pin "1") (pinfunction "S_1") (pintype "passive"))
      (node (ref "X9") (pin "1") (pinfunction "S_1") (pintype "passive"))
    )
    (net (code "68") (name "SEG_A_INA") (class "Default")
      (node (ref "R1") (pin "1") (pinfunction "1_1") (pintype "passive"))
      (node (ref "X1") (pin "1") (pinfunction "S_1") (pintype "passive"))
    )
    (net (code "69") (name "SEG_B_A") (class "Default")
      (node (ref "Q6") (pin "C") (pinfunction "C_C") (pintype "passive"))
      (node (ref "X2") (pin "2") (pinfunction "S_2") (pintype "passive"))
      (node (ref "X3") (pin "2") (pinfunction "S_2") (pintype "passive"))
      (node (ref "X4") (pin "2") (pinfunction "S_2") (pintype "passive"))
      (node (ref "X5") (pin "2") (pinfunction "S_2") (pintype "passive"))
      (node (ref "X6") (pin "2") (pinfunction "S_2") (pintype "passive"))
      (node (ref "X7") (pin "2") (pinfunction "S_2") (pintype "passive"))
      (node (ref "X8") (pin "2") (pinfunction "S_2") (pintype "passive"))
      (node (ref "X9") (pin "2") (pinfunction "S_2") (pintype "passive"))
    )
    (net (code "70") (name "SEG_B_INA") (class "Default")
      (node (ref "R5") (pin "1") (pinfunction "1_1") (pintype "passive"))
      (node (ref "X1") (pin "2") (pinfunction "S_2") (pintype "passive"))
    )
    (net (code "71") (name "SEG_C_A") (class "Default")
      (node (ref "Q10") (pin "C") (pinfunction "C_C") (pintype "passive"))
      (node (ref "X2") (pin "3") (pinfunction "S_3") (pintype "passive"))
      (node (ref "X3") (pin "3") (pinfunction "S_3") (pintype "passive"))
      (node (ref "X4") (pin "3") (pinfunction "S_3") (pintype "passive"))
      (node (ref "X5") (pin "3") (pinfunction "S_3") (pintype "passive"))
      (node (ref "X6") (pin "3") (pinfunction "S_3") (pintype "passive"))
      (node (ref "X7") (pin "3") (pinfunction "S_3") (pintype "passive"))
      (node (ref "X8") (pin "3") (pinfunction "S_3") (pintype "passive"))
      (node (ref "X9") (pin "3") (pinfunction "S_3") (pintype "passive"))
    )
    (net (code "72") (name "SEG_C_INA") (class "Default")
      (node (ref "R9") (pin "1") (pinfunction "1_1") (pintype "passive"))
      (node (ref "X1") (pin "3") (pinfunction "S_3") (pintype "passive"))
    )
    (net (code "73") (name "SEG_DP_A") (class "Default")
      (node (ref "Q30") (pin "C") (pinfunction "C_C") (pintype "passive"))
      (node (ref "X2") (pin "8") (pinfunction "S_8") (pintype "passive"))
      (node (ref "X3") (pin "8") (pinfunction "S_8") (pintype "passive"))
      (node (ref "X4") (pin "8") (pinfunction "S_8") (pintype "passive"))
      (node (ref "X5") (pin "8") (pinfunction "S_8") (pintype "passive"))
      (node (ref "X6") (pin "8") (pinfunction "S_8") (pintype "passive"))
      (node (ref "X7") (pin "8") (pinfunction "S_8") (pintype "passive"))
      (node (ref "X8") (pin "8") (pinfunction "S_8") (pintype "passive"))
      (node (ref "X9") (pin "8") (pinfunction "S_8") (pintype "passive"))
    )
    (net (code "74") (name "SEG_DP_INA") (class "Default")
      (node (ref "R29") (pin "1") (pinfunction "1_1") (pintype "passive"))
      (node (ref "X1") (pin "8") (pinfunction "S_8") (pintype "passive"))
    )
    (net (code "75") (name "SEG_D_A") (class "Default")
      (node (ref "Q14") (pin "C") (pinfunction "C_C") (pintype "passive"))
      (node (ref "X2") (pin "4") (pinfunction "S_4") (pintype "passive"))
      (node (ref "X3") (pin "4") (pinfunction "S_4") (pintype "passive"))
      (node (ref "X4") (pin "4") (pinfunction "S_4") (pintype "passive"))
      (node (ref "X5") (pin "4") (pinfunction "S_4") (pintype "passive"))
      (node (ref "X6") (pin "4") (pinfunction "S_4") (pintype "passive"))
      (node (ref "X7") (pin "4") (pinfunction "S_4") (pintype "passive"))
      (node (ref "X8") (pin "4") (pinfunction "S_4") (pintype "passive"))
      (node (ref "X9") (pin "4") (pinfunction "S_4") (pintype "passive"))
    )
    (net (code "76") (name "SEG_D_INA") (class "Default")
      (node (ref "R13") (pin "1") (pinfunction "1_1") (pintype "passive"))
      (node (ref "X1") (pin "4") (pinfunction "S_4") (pintype "passive"))
    )
    (net (code "77") (name "SEG_E_A") (class "Default")
      (node (ref "Q18") (pin "C") (pinfunction "C_C") (pintype "passive"))
      (node (ref "X2") (pin "5") (pinfunction "S_5") (pintype "passive"))
      (node (ref "X3") (pin "5") (pinfunction "S_5") (pintype "passive"))
      (node (ref "X4") (pin "5") (pinfunction "S_5") (pintype "passive"))
      (node (ref "X5") (pin "5") (pinfunction "S_5") (pintype "passive"))
      (node (ref "X6") (pin "5") (pinfunction "S_5") (pintype "passive"))
      (node (ref "X7") (pin "5") (pinfunction "S_5") (pintype "passive"))
      (node (ref "X8") (pin "5") (pinfunction "S_5") (pintype "passive"))
      (node (ref "X9") (pin "5") (pinfunction "S_5") (pintype "passive"))
    )
    (net (code "78") (name "SEG_E_INA") (class "Default")
      (node (ref "R17") (pin "1") (pinfunction "1_1") (pintype "passive"))
      (node (ref "X1") (pin "5") (pinfunction "S_5") (pintype "passive"))
    )
    (net (code "79") (name "SEG_F_A") (class "Default")
      (node (ref "Q22") (pin "C") (pinfunction "C_C") (pintype "passive"))
      (node (ref "X2") (pin "6") (pinfunction "S_6") (pintype "passive"))
      (node (ref "X3") (pin "6") (pinfunction "S_6") (pintype "passive"))
      (node (ref "X4") (pin "6") (pinfunction "S_6") (pintype "passive"))
      (node (ref "X5") (pin "6") (pinfunction "S_6") (pintype "passive"))
      (node (ref "X6") (pin "6") (pinfunction "S_6") (pintype "passive"))
      (node (ref "X7") (pin "6") (pinfunction "S_6") (pintype "passive"))
      (node (ref "X8") (pin "6") (pinfunction "S_6") (pintype "passive"))
      (node (ref "X9") (pin "6") (pinfunction "S_6") (pintype "passive"))
    )
    (net (code "80") (name "SEG_F_INA") (class "Default")
      (node (ref "R21") (pin "1") (pinfunction "1_1") (pintype "passive"))
      (node (ref "X1") (pin "6") (pinfunction "S_6") (pintype "passive"))
    )
    (net (code "81") (name "SEG_G_A") (class "Default")
      (node (ref "Q26") (pin "C") (pinfunction "C_C") (pintype "passive"))
      (node (ref "X2") (pin "7") (pinfunction "S_7") (pintype "passive"))
      (node (ref "X3") (pin "7") (pinfunction "S_7") (pintype "passive"))
      (node (ref "X4") (pin "7") (pinfunction "S_7") (pintype "passive"))
      (node (ref "X5") (pin "7") (pinfunction "S_7") (pintype "passive"))
      (node (ref "X6") (pin "7") (pinfunction "S_7") (pintype "passive"))
      (node (ref "X7") (pin "7") (pinfunction "S_7") (pintype "passive"))
      (node (ref "X8") (pin "7") (pinfunction "S_7") (pintype "passive"))
      (node (ref "X9") (pin "7") (pinfunction "S_7") (pintype "passive"))
    )
    (net (code "82") (name "SEG_G_INA") (class "Default")
      (node (ref "R25") (pin "1") (pinfunction "1_1") (pintype "passive"))
      (node (ref "X1") (pin "7") (pinfunction "S_7") (pintype "passive"))
    )
  )
)
